# Main.net
KiCad netlist of a schematic drawn in Altium Designer
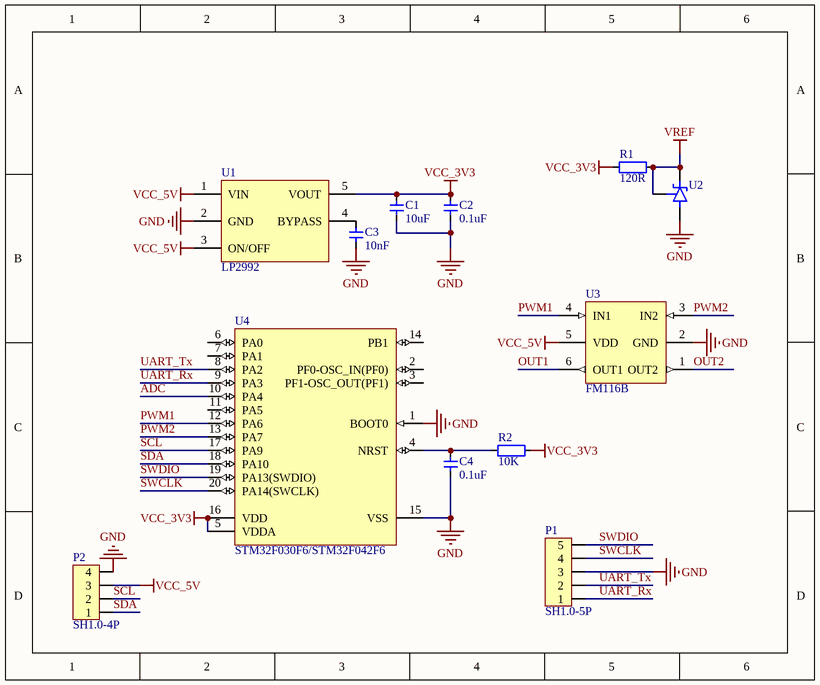
[diagram p0: Main.SchDoc]

(export (version "E")
  (design (tool "Eeschema 10.0.6"))
  (components
    (comp (ref "C1")
      (value "10uF")
      (footprint "CAP_0402")
      (description "Capacitor")
      (libsource (lib "MyPcbLib") (part "电容-0402"))
    )
    (comp (ref "C2")
      (value "0.1uF")
      (footprint "CAP_0402")
      (description "Capacitor")
      (libsource (lib "MyPcbLib") (part "电容-0402"))
    )
    (comp (ref "C3")
      (value "10nF")
      (footprint "CAP_0402")
      (description "Capacitor")
      (libsource (lib "MyPcbLib") (part "电容-0402"))
    )
    (comp (ref "C4")
      (value "0.1uF")
      (footprint "CAP_0402")
      (description "Capacitor")
      (libsource (lib "MyPcbLib") (part "电容-0402"))
    )
    (comp (ref "P1") (value "SH1.0-5P") (footprint "SH1.0-5P") (libsource (lib "MyPcbLib") (part "SH1.0-5P")))
    (comp (ref "P2") (value "SH1.0-4P") (footprint "SH1.0-4P") (libsource (lib "MyPcbLib") (part "SH1.0-4P")))
    (comp (ref "R1")
      (value "120R")
      (footprint "RES_0402")
      (description "Resistor")
      (libsource (lib "") (part "电阻-0402_1"))
    )
    (comp (ref "R2")
      (value "10K")
      (footprint "RES_0402")
      (description "Resistor")
      (libsource (lib "MyPcbLib") (part "电阻-0402"))
    )
    (comp (ref "U1")
      (value "LP2992")
      (footprint "SOT23-5")
      (description "LDO")
      (libsource (lib "MyPcbLib") (part "LP2992"))
    )
    (comp (ref "U2")
      (value "TL431IDBZT")
      (footprint "SOT23-3")
      (description "Adjustable precision shunt regulator 3-SOT-23 -40 to 85")
      (fields (field (name "MF") "Texas Instruments"))
      (libsource (lib "MyPcbLib") (part "TL431IDBZT"))
    )
    (comp (ref "U3")
      (value "FM116B")
      (footprint "SOT23-6")
      (fields (field (name "PARTNUMBER") "24LC256-I/ST"))
      (libsource (lib "MyPcbLib") (part "FM116B"))
    )
    (comp (ref "U4")
      (value "STM32F030F6/STM32F042F6")
      (footprint "TSSOP-20")
      (fields (field (name "PARTNUMBER") "STM32F030F4P6"))
      (libsource (lib "MyPcbLib") (part "STM32F030F4P6"))
    )
  )
  (nets
    (net (code "1") (name "/ADC") (class "Default")
      (node (ref "U4") (pin "10") (pinfunction "PA4_10") (pintype "bidirectional"))
    )
    (net (code "2") (name "/OUT1") (class "Default")
      (node (ref "U3") (pin "6") (pinfunction "OUT1_6") (pintype "output"))
    )
    (net (code "3") (name "/OUT2") (class "Default")
      (node (ref "U3") (pin "1") (pinfunction "OUT2_1") (pintype "output"))
    )
    (net (code "4") (name "/PWM1") (class "Default")
      (node (ref "U3") (pin "4") (pinfunction "IN1_4") (pintype "input"))
      (node (ref "U4") (pin "12") (pinfunction "PA6_12") (pintype "bidirectional"))
    )
    (net (code "5") (name "/PWM2") (class "Default")
      (node (ref "U3") (pin "3") (pinfunction "IN2_3") (pintype "input"))
      (node (ref "U4") (pin "13") (pinfunction "PA7_13") (pintype "bidirectional"))
    )
    (net (code "6") (name "/SCL") (class "Default")
      (node (ref "P2") (pin "2") (pinfunction "2_2") (pintype "passive"))
      (node (ref "U4") (pin "17") (pinfunction "PA9_17") (pintype "bidirectional"))
    )
    (net (code "7") (name "/SDA") (class "Default")
      (node (ref "P2") (pin "1") (pinfunction "1_1") (pintype "passive"))
      (node (ref "U4") (pin "18") (pinfunction "PA10_18") (pintype "bidirectional"))
    )
    (net (code "8") (name "/SWCLK") (class "Default")
      (node (ref "P1") (pin "4") (pinfunction "4_4") (pintype "passive"))
      (node (ref "U4") (pin "20") (pinfunction "PA14(SWCLK)_20") (pintype "bidirectional"))
    )
    (net (code "9") (name "/SWDIO") (class "Default")
      (node (ref "P1") (pin "5") (pinfunction "5_5") (pintype "passive"))
      (node (ref "U4") (pin "19") (pinfunction "PA13(SWDIO)_19") (pintype "bidirectional"))
    )
    (net (code "10") (name "/UART_Rx") (class "Default")
      (node (ref "P1") (pin "1") (pinfunction "1_1") (pintype "passive"))
      (node (ref "U4") (pin "9") (pinfunction "PA3_9") (pintype "bidirectional"))
    )
    (net (code "11") (name "/UART_Tx") (class "Default")
      (node (ref "P1") (pin "2") (pinfunction "2_2") (pintype "passive"))
      (node (ref "U4") (pin "8") (pinfunction "PA2_8") (pintype "bidirectional"))
    )
    (net (code "12") (name "GND") (class "Default")
      (node (ref "C1") (pin "1") (pinfunction "1_1") (pintype "passive"))
      (node (ref "C2") (pin "1") (pinfunction "1_1") (pintype "passive"))
      (node (ref "C3") (pin "2") (pinfunction "2_2") (pintype "passive"))
      (node (ref "C4") (pin "1") (pinfunction "1_1") (pintype "passive"))
      (node (ref "P1") (pin "3") (pinfunction "3_3") (pintype "passive"))
      (node (ref "P2") (pin "4") (pinfunction "4_4") (pintype "passive"))
      (node (ref "U1") (pin "2") (pinfunction "GND_2") (pintype "passive"))
      (node (ref "U2") (pin "3") (pinfunction "ANODE_3") (pintype "passive"))
      (node (ref "U3") (pin "2") (pinfunction "GND_2") (pintype "power_in"))
      (node (ref "U4") (pin "1") (pinfunction "BOOT0_1") (pintype "input"))
      (node (ref "U4") (pin "15") (pinfunction "VSS_15") (pintype "power_in"))
    )
    (net (code "13") (name "Net-(U1-BYPASS)") (class "Default")
      (node (ref "C3") (pin "1") (pinfunction "1_1") (pintype "passive"))
      (node (ref "U1") (pin "4") (pinfunction "BYPASS_4") (pintype "passive"))
    )
    (net (code "14") (name "Net-(U4-NRST)") (class "Default")
      (node (ref "C4") (pin "2") (pinfunction "2_2") (pintype "passive"))
      (node (ref "R2") (pin "2") (pinfunction "2_2") (pintype "passive"))
      (node (ref "U4") (pin "4") (pinfunction "NRST_4") (pintype "bidirectional"))
    )
    (net (code "15") (name "VCC_3V3") (class "Default")
      (node (ref "C1") (pin "2") (pinfunction "2_2") (pintype "passive"))
      (node (ref "C2") (pin "2") (pinfunction "2_2") (pintype "passive"))
      (node (ref "R1") (pin "1") (pinfunction "1_1") (pintype "passive"))
      (node (ref "R2") (pin "1") (pinfunction "1_1") (pintype "passive"))
      (node (ref "U1") (pin "5") (pinfunction "VOUT_5") (pintype "passive"))
      (node (ref "U4") (pin "16") (pinfunction "VDD_16") (pintype "power_in"))
      (node (ref "U4") (pin "5") (pinfunction "VDDA_5") (pintype "power_in"))
    )
    (net (code "16") (name "VCC_5V") (class "Default")
      (node (ref "P2") (pin "3") (pinfunction "3_3") (pintype "passive"))
      (node (ref "U1") (pin "1") (pinfunction "VIN_1") (pintype "passive"))
      (node (ref "U1") (pin "3") (pinfunction "ON/OFF_3") (pintype "passive"))
      (node (ref "U3") (pin "5") (pinfunction "VDD_5") (pintype "power_in"))
    )
    (net (code "17") (name "VREF") (class "Default")
      (node (ref "R1") (pin "2") (pinfunction "2_2") (pintype "passive"))
      (node (ref "U2") (pin "1") (pinfunction "CATHODE_1") (pintype "passive"))
      (node (ref "U2") (pin "2") (pinfunction "REF_2") (pintype "passive"))
    )
    (net (code "18") (name "unconnected-(U4-PA0-Pad6)") (class "Default")
      (node (ref "U4") (pin "6") (pinfunction "PA0_6") (pintype "bidirectional"))
    )
    (net (code "19") (name "unconnected-(U4-PA1-Pad7)") (class "Default")
      (node (ref "U4") (pin "7") (pinfunction "PA1_7") (pintype "bidirectional"))
    )
    (net (code "20") (name "unconnected-(U4-PA5-Pad11)") (class "Default")
      (node (ref "U4") (pin "11") (pinfunction "PA5_11") (pintype "bidirectional"))
    )
    (net (code "21") (name "unconnected-(U4-PB1-Pad14)") (class "Default")
      (node (ref "U4") (pin "14") (pinfunction "PB1_14") (pintype "bidirectional"))
    )
    (net (code "22") (name "unconnected-(U4-PF0-OSC_IN(PF0)-Pad2)") (class "Default")
      (node (ref "U4") (pin "2") (pinfunction "PF0-OSC_IN(PF0)_2") (pintype "bidirectional"))
    )
    (net (code "23") (name "unconnected-(U4-PF1-OSC_OUT(PF1)-Pad3)") (class "Default")
      (node (ref "U4") (pin "3") (pinfunction "PF1-OSC_OUT(PF1)_3") (pintype "bidirectional"))
    )
  )
)
